# ICDI_Bridge.net
KiCad netlist of a schematic drawn in EAGLE
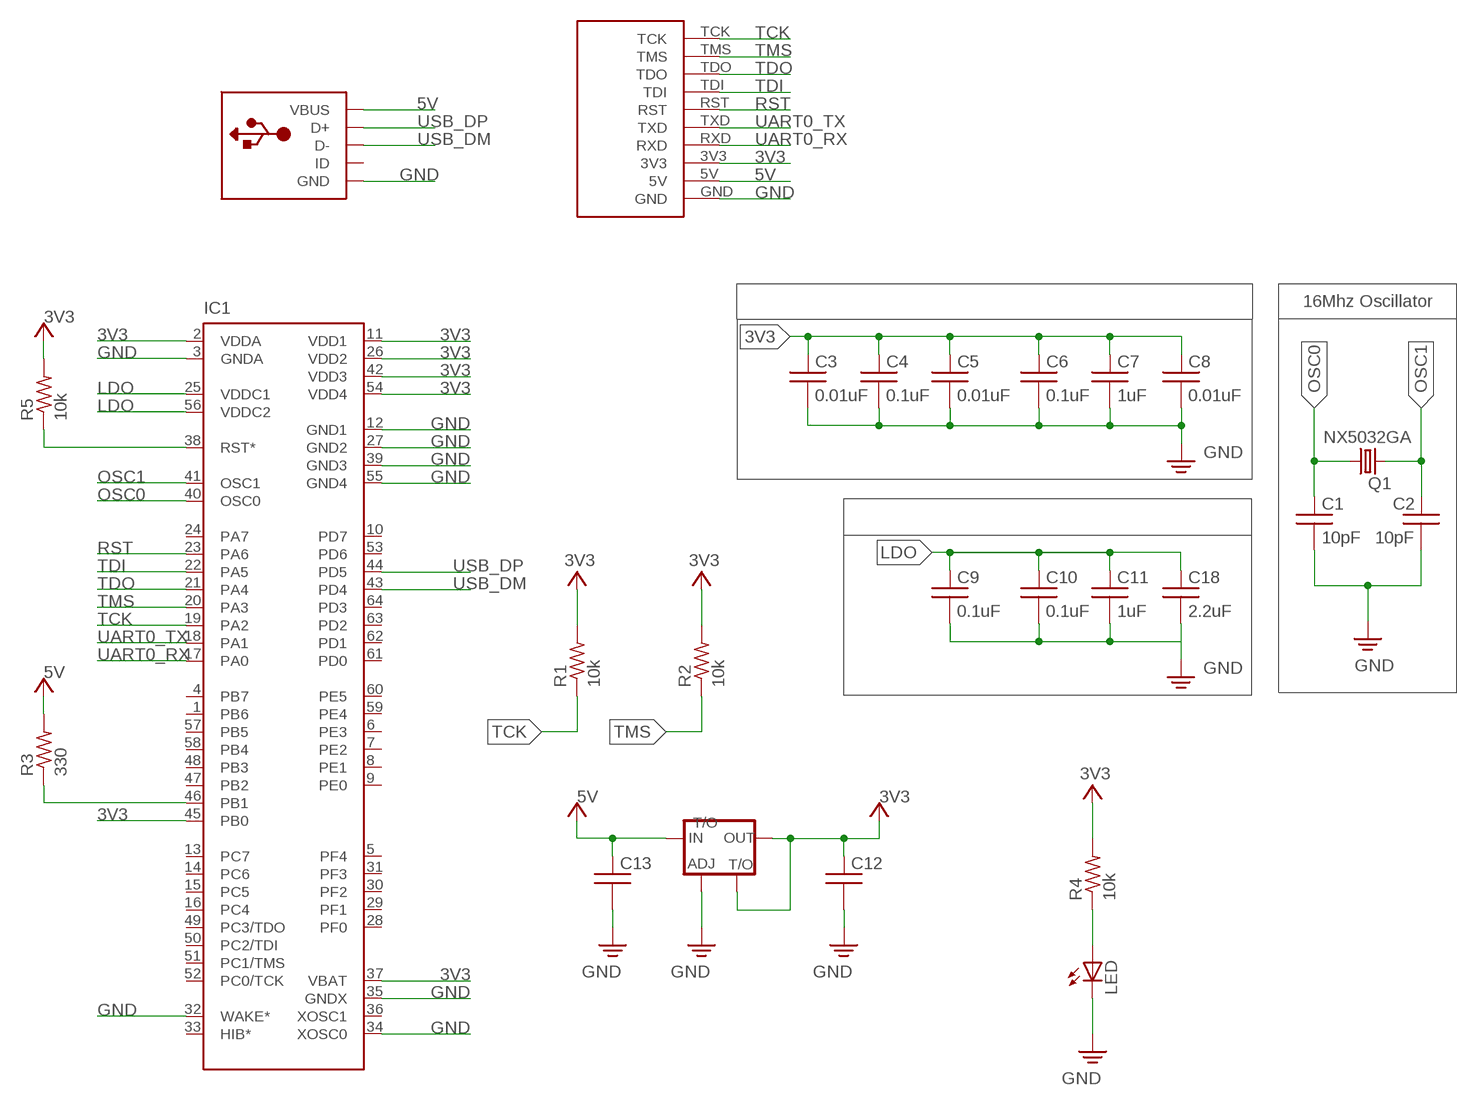
[diagram p0: schematic, sheet 1]

(export (version "E")
  (design (tool "Eeschema 10.0.6"))
  (components
    (comp (ref "C1")
      (value "10pF")
      (footprint "eagle-import:C0603K")
      (libsource (lib "eagle-import") (part "CAPACITORC0603K"))
    )
    (comp (ref "C2")
      (value "10pF")
      (footprint "eagle-import:C0603K")
      (libsource (lib "eagle-import") (part "CAPACITORC0603K"))
    )
    (comp (ref "C3")
      (value "0.01uF")
      (footprint "eagle-import:C0603K")
      (libsource (lib "eagle-import") (part "CAPACITORC0603K"))
    )
    (comp (ref "C4")
      (value "0.1uF")
      (footprint "eagle-import:C0603K")
      (libsource (lib "eagle-import") (part "CAPACITORC0603K"))
    )
    (comp (ref "C5")
      (value "0.01uF")
      (footprint "eagle-import:C0603K")
      (libsource (lib "eagle-import") (part "CAPACITORC0603K"))
    )
    (comp (ref "C6")
      (value "0.1uF")
      (footprint "eagle-import:C0603K")
      (libsource (lib "eagle-import") (part "CAPACITORC0603K"))
    )
    (comp (ref "C7")
      (value "1uF")
      (footprint "eagle-import:C0603K")
      (libsource (lib "eagle-import") (part "CAPACITORC0603K"))
    )
    (comp (ref "C8")
      (value "0.01uF")
      (footprint "eagle-import:C0603K")
      (libsource (lib "eagle-import") (part "CAPACITORC0603K"))
    )
    (comp (ref "C9")
      (value "0.1uF")
      (footprint "eagle-import:C0603K")
      (libsource (lib "eagle-import") (part "CAPACITORC0603K"))
    )
    (comp (ref "C10")
      (value "0.1uF")
      (footprint "eagle-import:C0603K")
      (libsource (lib "eagle-import") (part "CAPACITORC0603K"))
    )
    (comp (ref "C11")
      (value "1uF")
      (footprint "eagle-import:C0603K")
      (libsource (lib "eagle-import") (part "CAPACITORC0603K"))
    )
    (comp (ref "C12")
      (value "CAPACITORC0805K")
      (footprint "eagle-import:C0805K")
      (libsource (lib "eagle-import") (part "CAPACITORC0805K"))
    )
    (comp (ref "C13")
      (value "CAPACITORC0603K")
      (footprint "eagle-import:C0603K")
      (libsource (lib "eagle-import") (part "CAPACITORC0603K"))
    )
    (comp (ref "C18")
      (value "2.2uF")
      (footprint "eagle-import:C0603K")
      (libsource (lib "eagle-import") (part "CAPACITORC0603K"))
    )
    (comp (ref "IC1")
      (value "TM4C123GH6PM")
      (footprint "eagle-import:SQFP-S-10X10-64")
      (libsource (lib "eagle-import") (part "TM4C123GH6PM"))
    )
    (comp (ref "LED")
      (value "LEDCHIPLED_0603")
      (footprint "eagle-import:CHIPLED_0603")
      (libsource (lib "eagle-import") (part "LEDCHIPLED_0603"))
    )
    (comp (ref "Q1")
      (value "NX5032GA")
      (footprint "eagle-import:NX5032GA")
      (libsource (lib "eagle-import") (part "NX5032GA"))
    )
    (comp (ref "R1")
      (value "10k")
      (footprint "eagle-import:R0603")
      (libsource (lib "eagle-import") (part "RESISTORR0603"))
    )
    (comp (ref "R2")
      (value "10k")
      (footprint "eagle-import:R0603")
      (libsource (lib "eagle-import") (part "RESISTORR0603"))
    )
    (comp (ref "R3")
      (value "330")
      (footprint "eagle-import:R0603")
      (libsource (lib "eagle-import") (part "RESISTORR0603"))
    )
    (comp (ref "R4")
      (value "10k")
      (footprint "eagle-import:R0603")
      (libsource (lib "eagle-import") (part "RESISTORR0603"))
    )
    (comp (ref "R5")
      (value "10k")
      (footprint "eagle-import:R0603")
      (libsource (lib "eagle-import") (part "RESISTORR0603"))
    )
    (comp (ref "U$1")
      (value "USB_MICRO_PTH")
      (footprint "eagle-import:USB_MICRO_PTH")
      (libsource (lib "eagle-import") (part "USB_MICRO_PTH"))
    )
    (comp (ref "U$2")
      (value "JTAG_SERIAL")
      (footprint "eagle-import:JTAG_SERIAL_PTH")
      (libsource (lib "eagle-import") (part "JTAG_SERIAL"))
    )
    (comp (ref "U$4")
      (value "_VOLTAGE_REGULATOR_AMS1117")
      (footprint "eagle-import:_PACKAGE_SOT223")
      (libsource (lib "eagle-import") (part "_VOLTAGE_REGULATOR_AMS1117"))
    )
  )
  (nets
    (net (code "1") (name "+5V") (class "Default")
      (node (ref "C13") (pin "1") (pinfunction "1_1") (pintype "passive"))
      (node (ref "R3") (pin "2") (pinfunction "2_2") (pintype "passive"))
      (node (ref "U$1") (pin "1") (pinfunction "VBUS_1") (pintype "power_in"))
      (node (ref "U$2") (pin "5V") (pinfunction "5V_5V") (pintype "bidirectional"))
      (node (ref "U$4") (pin "3") (pinfunction "IN_3") (pintype "input"))
    )
    (net (code "2") (name "/RST") (class "Default")
      (node (ref "IC1") (pin "23") (pinfunction "PA6_23") (pintype "bidirectional"))
      (node (ref "U$2") (pin "RST") (pinfunction "RST_RST") (pintype "bidirectional"))
    )
    (net (code "3") (name "/TDI") (class "Default")
      (node (ref "IC1") (pin "22") (pinfunction "PA5_22") (pintype "bidirectional"))
      (node (ref "U$2") (pin "TDI") (pinfunction "TDI_TDI") (pintype "bidirectional"))
    )
    (net (code "4") (name "/TDO") (class "Default")
      (node (ref "IC1") (pin "21") (pinfunction "PA4_21") (pintype "bidirectional"))
      (node (ref "U$2") (pin "TDO") (pinfunction "TDO_TDO") (pintype "bidirectional"))
    )
    (net (code "5") (name "/UART0_RX") (class "Default")
      (node (ref "IC1") (pin "17") (pinfunction "PA0_17") (pintype "bidirectional"))
      (node (ref "U$2") (pin "RXD") (pinfunction "RXD_RXD") (pintype "bidirectional"))
    )
    (net (code "6") (name "/UART0_TX") (class "Default")
      (node (ref "IC1") (pin "18") (pinfunction "PA1_18") (pintype "bidirectional"))
      (node (ref "U$2") (pin "TXD") (pinfunction "TXD_TXD") (pintype "bidirectional"))
    )
    (net (code "7") (name "/USB_DM") (class "Default")
      (node (ref "IC1") (pin "43") (pinfunction "PD4_43") (pintype "bidirectional"))
      (node (ref "U$1") (pin "2") (pinfunction "D-_2") (pintype "bidirectional"))
    )
    (net (code "8") (name "/USB_DP") (class "Default")
      (node (ref "IC1") (pin "44") (pinfunction "PD5_44") (pintype "bidirectional"))
      (node (ref "U$1") (pin "3") (pinfunction "D+_3") (pintype "bidirectional"))
    )
    (net (code "9") (name "3V3") (class "Default")
      (node (ref "C12") (pin "1") (pinfunction "1_1") (pintype "passive"))
      (node (ref "C3") (pin "1") (pinfunction "1_1") (pintype "passive"))
      (node (ref "C4") (pin "1") (pinfunction "1_1") (pintype "passive"))
      (node (ref "C5") (pin "1") (pinfunction "1_1") (pintype "passive"))
      (node (ref "C6") (pin "1") (pinfunction "1_1") (pintype "passive"))
      (node (ref "C7") (pin "1") (pinfunction "1_1") (pintype "passive"))
      (node (ref "C8") (pin "1") (pinfunction "1_1") (pintype "passive"))
      (node (ref "IC1") (pin "11") (pinfunction "VDD1_11") (pintype "power_in"))
      (node (ref "IC1") (pin "2") (pinfunction "VDDA_2") (pintype "power_in"))
      (node (ref "IC1") (pin "26") (pinfunction "VDD2_26") (pintype "power_in"))
      (node (ref "IC1") (pin "37") (pinfunction "VBAT_37") (pintype "power_in"))
      (node (ref "IC1") (pin "42") (pinfunction "VDD3_42") (pintype "power_in"))
      (node (ref "IC1") (pin "45") (pinfunction "PB0_45") (pintype "bidirectional"))
      (node (ref "IC1") (pin "54") (pinfunction "VDD4_54") (pintype "power_in"))
      (node (ref "R1") (pin "2") (pinfunction "2_2") (pintype "passive"))
      (node (ref "R2") (pin "2") (pinfunction "2_2") (pintype "passive"))
      (node (ref "R4") (pin "2") (pinfunction "2_2") (pintype "passive"))
      (node (ref "R5") (pin "2") (pinfunction "2_2") (pintype "passive"))
      (node (ref "U$2") (pin "3V3") (pinfunction "3V3_3V3") (pintype "bidirectional"))
      (node (ref "U$4") (pin "2") (pinfunction "OUT_2") (pintype "output"))
      (node (ref "U$4") (pin "4") (pinfunction "T/O_4") (pintype "input"))
    )
    (net (code "10") (name "GND") (class "Default")
      (node (ref "C1") (pin "2") (pinfunction "2_2") (pintype "passive"))
      (node (ref "C10") (pin "2") (pinfunction "2_2") (pintype "passive"))
      (node (ref "C11") (pin "2") (pinfunction "2_2") (pintype "passive"))
      (node (ref "C12") (pin "2") (pinfunction "2_2") (pintype "passive"))
      (node (ref "C13") (pin "2") (pinfunction "2_2") (pintype "passive"))
      (node (ref "C18") (pin "2") (pinfunction "2_2") (pintype "passive"))
      (node (ref "C2") (pin "2") (pinfunction "2_2") (pintype "passive"))
      (node (ref "C3") (pin "2") (pinfunction "2_2") (pintype "passive"))
      (node (ref "C4") (pin "2") (pinfunction "2_2") (pintype "passive"))
      (node (ref "C5") (pin "2") (pinfunction "2_2") (pintype "passive"))
      (node (ref "C6") (pin "2") (pinfunction "2_2") (pintype "passive"))
      (node (ref "C7") (pin "2") (pinfunction "2_2") (pintype "passive"))
      (node (ref "C8") (pin "2") (pinfunction "2_2") (pintype "passive"))
      (node (ref "C9") (pin "2") (pinfunction "2_2") (pintype "passive"))
      (node (ref "IC1") (pin "12") (pinfunction "GND1_12") (pintype "power_in"))
      (node (ref "IC1") (pin "27") (pinfunction "GND2_27") (pintype "power_in"))
      (node (ref "IC1") (pin "3") (pinfunction "GNDA_3") (pintype "power_in"))
      (node (ref "IC1") (pin "32") (pinfunction "WAKE*_32") (pintype "input"))
      (node (ref "IC1") (pin "34") (pinfunction "XOSC0_34") (pintype "passive"))
      (node (ref "IC1") (pin "35") (pinfunction "GNDX_35") (pintype "power_in"))
      (node (ref "IC1") (pin "39") (pinfunction "GND3_39") (pintype "power_in"))
      (node (ref "IC1") (pin "55") (pinfunction "GND4_55") (pintype "power_in"))
      (node (ref "LED") (pin "C") (pinfunction "C_C") (pintype "passive"))
      (node (ref "U$1") (pin "5") (pinfunction "GND_5") (pintype "power_in"))
      (node (ref "U$2") (pin "GND") (pinfunction "GND_GND") (pintype "bidirectional"))
      (node (ref "U$4") (pin "1") (pinfunction "ADJ_1") (pintype "input"))
    )
    (net (code "11") (name "LDO") (class "Default")
      (node (ref "C10") (pin "1") (pinfunction "1_1") (pintype "passive"))
      (node (ref "C11") (pin "1") (pinfunction "1_1") (pintype "passive"))
      (node (ref "C18") (pin "1") (pinfunction "1_1") (pintype "passive"))
      (node (ref "C9") (pin "1") (pinfunction "1_1") (pintype "passive"))
      (node (ref "IC1") (pin "25") (pinfunction "VDDC1_25") (pintype "power_in"))
      (node (ref "IC1") (pin "56") (pinfunction "VDDC2_56") (pintype "power_in"))
    )
    (net (code "12") (name "Net-(IC1-PB1)") (class "Default")
      (node (ref "IC1") (pin "46") (pinfunction "PB1_46") (pintype "bidirectional"))
      (node (ref "R3") (pin "1") (pinfunction "1_1") (pintype "passive"))
    )
    (net (code "13") (name "Net-(IC1-RST*)") (class "Default")
      (node (ref "IC1") (pin "38") (pinfunction "RST*_38") (pintype "input"))
      (node (ref "R5") (pin "1") (pinfunction "1_1") (pintype "passive"))
    )
    (net (code "14") (name "Net-(LED-PadA)") (class "Default")
      (node (ref "LED") (pin "A") (pinfunction "A_A") (pintype "passive"))
      (node (ref "R4") (pin "1") (pinfunction "1_1") (pintype "passive"))
    )
    (net (code "15") (name "OSC0") (class "Default")
      (node (ref "C1") (pin "1") (pinfunction "1_1") (pintype "passive"))
      (node (ref "IC1") (pin "40") (pinfunction "OSC0_40") (pintype "passive"))
      (node (ref "Q1") (pin "1") (pinfunction "1_1") (pintype "passive"))
    )
    (net (code "16") (name "OSC1") (class "Default")
      (node (ref "C2") (pin "1") (pinfunction "1_1") (pintype "passive"))
      (node (ref "IC1") (pin "41") (pinfunction "OSC1_41") (pintype "passive"))
      (node (ref "Q1") (pin "2") (pinfunction "2_2") (pintype "passive"))
    )
    (net (code "17") (name "TCK") (class "Default")
      (node (ref "IC1") (pin "19") (pinfunction "PA2_19") (pintype "bidirectional"))
      (node (ref "R1") (pin "1") (pinfunction "1_1") (pintype "passive"))
      (node (ref "U$2") (pin "TCK") (pinfunction "TCK_TCK") (pintype "bidirectional"))
    )
    (net (code "18") (name "TMS") (class "Default")
      (node (ref "IC1") (pin "20") (pinfunction "PA3_20") (pintype "bidirectional"))
      (node (ref "R2") (pin "1") (pinfunction "1_1") (pintype "passive"))
      (node (ref "U$2") (pin "TMS") (pinfunction "TMS_TMS") (pintype "bidirectional"))
    )
    (net (code "19") (name "unconnected-(IC1-HIB*-Pad33)") (class "Default")
      (node (ref "IC1") (pin "33") (pinfunction "HIB*_33") (pintype "bidirectional"))
    )
    (net (code "20") (name "unconnected-(IC1-PA7-Pad24)") (class "Default")
      (node (ref "IC1") (pin "24") (pinfunction "PA7_24") (pintype "bidirectional"))
    )
    (net (code "21") (name "unconnected-(IC1-PB2-Pad47)") (class "Default")
      (node (ref "IC1") (pin "47") (pinfunction "PB2_47") (pintype "bidirectional"))
    )
    (net (code "22") (name "unconnected-(IC1-PB3-Pad48)") (class "Default")
      (node (ref "IC1") (pin "48") (pinfunction "PB3_48") (pintype "bidirectional"))
    )
    (net (code "23") (name "unconnected-(IC1-PB4-Pad58)") (class "Default")
      (node (ref "IC1") (pin "58") (pinfunction "PB4_58") (pintype "bidirectional"))
    )
    (net (code "24") (name "unconnected-(IC1-PB5-Pad57)") (class "Default")
      (node (ref "IC1") (pin "57") (pinfunction "PB5_57") (pintype "bidirectional"))
    )
    (net (code "25") (name "unconnected-(IC1-PB6-Pad1)") (class "Default")
      (node (ref "IC1") (pin "1") (pinfunction "PB6_1") (pintype "bidirectional"))
    )
    (net (code "26") (name "unconnected-(IC1-PB7-Pad4)") (class "Default")
      (node (ref "IC1") (pin "4") (pinfunction "PB7_4") (pintype "bidirectional"))
    )
    (net (code "27") (name "unconnected-(IC1-PC0{slash}TCK-Pad52)") (class "Default")
      (node (ref "IC1") (pin "52") (pinfunction "PC0/TCK_52") (pintype "bidirectional"))
    )
    (net (code "28") (name "unconnected-(IC1-PC1{slash}TMS-Pad51)") (class "Default")
      (node (ref "IC1") (pin "51") (pinfunction "PC1/TMS_51") (pintype "bidirectional"))
    )
    (net (code "29") (name "unconnected-(IC1-PC2{slash}TDI-Pad50)") (class "Default")
      (node (ref "IC1") (pin "50") (pinfunction "PC2/TDI_50") (pintype "bidirectional"))
    )
    (net (code "30") (name "unconnected-(IC1-PC3{slash}TDO-Pad49)") (class "Default")
      (node (ref "IC1") (pin "49") (pinfunction "PC3/TDO_49") (pintype "bidirectional"))
    )
    (net (code "31") (name "unconnected-(IC1-PC4-Pad16)") (class "Default")
      (node (ref "IC1") (pin "16") (pinfunction "PC4_16") (pintype "bidirectional"))
    )
    (net (code "32") (name "unconnected-(IC1-PC5-Pad15)") (class "Default")
      (node (ref "IC1") (pin "15") (pinfunction "PC5_15") (pintype "bidirectional"))
    )
    (net (code "33") (name "unconnected-(IC1-PC6-Pad14)") (class "Default")
      (node (ref "IC1") (pin "14") (pinfunction "PC6_14") (pintype "bidirectional"))
    )
    (net (code "34") (name "unconnected-(IC1-PC7-Pad13)") (class "Default")
      (node (ref "IC1") (pin "13") (pinfunction "PC7_13") (pintype "bidirectional"))
    )
    (net (code "35") (name "unconnected-(IC1-PD0-Pad61)") (class "Default")
      (node (ref "IC1") (pin "61") (pinfunction "PD0_61") (pintype "bidirectional"))
    )
    (net (code "36") (name "unconnected-(IC1-PD1-Pad62)") (class "Default")
      (node (ref "IC1") (pin "62") (pinfunction "PD1_62") (pintype "bidirectional"))
    )
    (net (code "37") (name "unconnected-(IC1-PD2-Pad63)") (class "Default")
      (node (ref "IC1") (pin "63") (pinfunction "PD2_63") (pintype "bidirectional"))
    )
    (net (code "38") (name "unconnected-(IC1-PD3-Pad64)") (class "Default")
      (node (ref "IC1") (pin "64") (pinfunction "PD3_64") (pintype "bidirectional"))
    )
    (net (code "39") (name "unconnected-(IC1-PD6-Pad53)") (class "Default")
      (node (ref "IC1") (pin "53") (pinfunction "PD6_53") (pintype "bidirectional"))
    )
    (net (code "40") (name "unconnected-(IC1-PD7-Pad10)") (class "Default")
      (node (ref "IC1") (pin "10") (pinfunction "PD7_10") (pintype "bidirectional"))
    )
    (net (code "41") (name "unconnected-(IC1-PE0-Pad9)") (class "Default")
      (node (ref "IC1") (pin "9") (pinfunction "PE0_9") (pintype "bidirectional"))
    )
    (net (code "42") (name "unconnected-(IC1-PE1-Pad8)") (class "Default")
      (node (ref "IC1") (pin "8") (pinfunction "PE1_8") (pintype "bidirectional"))
    )
    (net (code "43") (name "unconnected-(IC1-PE2-Pad7)") (class "Default")
      (node (ref "IC1") (pin "7") (pinfunction "PE2_7") (pintype "bidirectional"))
    )
    (net (code "44") (name "unconnected-(IC1-PE3-Pad6)") (class "Default")
      (node (ref "IC1") (pin "6") (pinfunction "PE3_6") (pintype "bidirectional"))
    )
    (net (code "45") (name "unconnected-(IC1-PE4-Pad59)") (class "Default")
      (node (ref "IC1") (pin "59") (pinfunction "PE4_59") (pintype "bidirectional"))
    )
    (net (code "46") (name "unconnected-(IC1-PE5-Pad60)") (class "Default")
      (node (ref "IC1") (pin "60") (pinfunction "PE5_60") (pintype "bidirectional"))
    )
    (net (code "47") (name "unconnected-(IC1-PF0-Pad28)") (class "Default")
      (node (ref "IC1") (pin "28") (pinfunction "PF0_28") (pintype "bidirectional"))
    )
    (net (code "48") (name "unconnected-(IC1-PF1-Pad29)") (class "Default")
      (node (ref "IC1") (pin "29") (pinfunction "PF1_29") (pintype "bidirectional"))
    )
    (net (code "49") (name "unconnected-(IC1-PF2-Pad30)") (class "Default")
      (node (ref "IC1") (pin "30") (pinfunction "PF2_30") (pintype "bidirectional"))
    )
    (net (code "50") (name "unconnected-(IC1-PF3-Pad31)") (class "Default")
      (node (ref "IC1") (pin "31") (pinfunction "PF3_31") (pintype "bidirectional"))
    )
    (net (code "51") (name "unconnected-(IC1-PF4-Pad5)") (class "Default")
      (node (ref "IC1") (pin "5") (pinfunction "PF4_5") (pintype "bidirectional"))
    )
    (net (code "52") (name "unconnected-(IC1-XOSC1-Pad36)") (class "Default")
      (node (ref "IC1") (pin "36") (pinfunction "XOSC1_36") (pintype "passive"))
    )
    (net (code "53") (name "unconnected-(U$1-ID-Pad4)") (class "Default")
      (node (ref "U$1") (pin "4") (pinfunction "ID_4") (pintype "bidirectional"))
    )
  )
)
